# TSSOP16_a_DIP.net
KiCad netlist of a schematic drawn in EAGLE
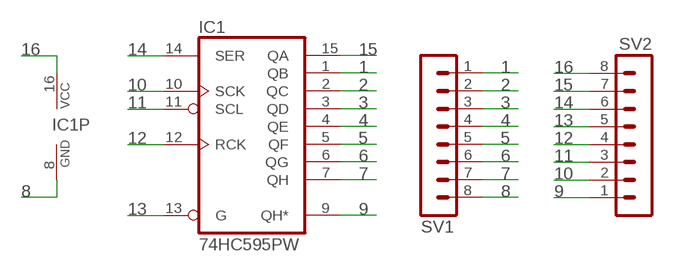
[diagram p0: schematic, sheet 1]

(export (version "E")
  (design (tool "Eeschema 10.0.6"))
  (components
    (comp (ref "IC1")
      (value "74HC595PW")
      (footprint "eagle-import:TSSOP16")
      (libsource (lib "eagle-import") (part "74595PWHC"))
    )
    (comp (ref "SV1")
      (value "MA08-1")
      (footprint "eagle-import:MA08-1")
      (libsource (lib "eagle-import") (part "MA08-1"))
    )
    (comp (ref "SV2")
      (value "MA08-1")
      (footprint "eagle-import:MA08-1")
      (libsource (lib "eagle-import") (part "MA08-1"))
    )
  )
  (nets
    (net (code "1") (name "/1") (class "Default")
      (node (ref "IC1") (pin "1") (pinfunction "QB_1") (pintype "tri_state"))
      (node (ref "SV1") (pin "1") (pinfunction "1_1") (pintype "passive"))
    )
    (net (code "2") (name "/2") (class "Default")
      (node (ref "IC1") (pin "2") (pinfunction "QC_2") (pintype "tri_state"))
      (node (ref "SV1") (pin "2") (pinfunction "2_2") (pintype "passive"))
    )
    (net (code "3") (name "/3") (class "Default")
      (node (ref "IC1") (pin "3") (pinfunction "QD_3") (pintype "tri_state"))
      (node (ref "SV1") (pin "3") (pinfunction "3_3") (pintype "passive"))
    )
    (net (code "4") (name "/4") (class "Default")
      (node (ref "IC1") (pin "4") (pinfunction "QE_4") (pintype "tri_state"))
      (node (ref "SV1") (pin "4") (pinfunction "4_4") (pintype "passive"))
    )
    (net (code "5") (name "/5") (class "Default")
      (node (ref "IC1") (pin "5") (pinfunction "QF_5") (pintype "tri_state"))
      (node (ref "SV1") (pin "5") (pinfunction "5_5") (pintype "passive"))
    )
    (net (code "6") (name "/6") (class "Default")
      (node (ref "IC1") (pin "6") (pinfunction "QG_6") (pintype "tri_state"))
      (node (ref "SV1") (pin "6") (pinfunction "6_6") (pintype "passive"))
    )
    (net (code "7") (name "/7") (class "Default")
      (node (ref "IC1") (pin "7") (pinfunction "QH_7") (pintype "tri_state"))
      (node (ref "SV1") (pin "7") (pinfunction "7_7") (pintype "passive"))
    )
    (net (code "8") (name "/8") (class "Default")
      (node (ref "IC1") (pin "8") (pinfunction "GND_8") (pintype "power_in"))
      (node (ref "SV1") (pin "8") (pinfunction "8_8") (pintype "passive"))
    )
    (net (code "9") (name "/9") (class "Default")
      (node (ref "IC1") (pin "9") (pinfunction "QH*_9") (pintype "tri_state"))
      (node (ref "SV2") (pin "1") (pinfunction "1_1") (pintype "passive"))
    )
    (net (code "10") (name "/10") (class "Default")
      (node (ref "IC1") (pin "10") (pinfunction "SCK_10") (pintype "input"))
      (node (ref "SV2") (pin "2") (pinfunction "2_2") (pintype "passive"))
    )
    (net (code "11") (name "/11") (class "Default")
      (node (ref "IC1") (pin "11") (pinfunction "SCL_11") (pintype "input"))
      (node (ref "SV2") (pin "3") (pinfunction "3_3") (pintype "passive"))
    )
    (net (code "12") (name "/12") (class "Default")
      (node (ref "IC1") (pin "12") (pinfunction "RCK_12") (pintype "input"))
      (node (ref "SV2") (pin "4") (pinfunction "4_4") (pintype "passive"))
    )
    (net (code "13") (name "/13") (class "Default")
      (node (ref "IC1") (pin "13") (pinfunction "G_13") (pintype "input"))
      (node (ref "SV2") (pin "5") (pinfunction "5_5") (pintype "passive"))
    )
    (net (code "14") (name "/14") (class "Default")
      (node (ref "IC1") (pin "14") (pinfunction "SER_14") (pintype "input"))
      (node (ref "SV2") (pin "6") (pinfunction "6_6") (pintype "passive"))
    )
    (net (code "15") (name "/15") (class "Default")
      (node (ref "IC1") (pin "15") (pinfunction "QA_15") (pintype "tri_state"))
      (node (ref "SV2") (pin "7") (pinfunction "7_7") (pintype "passive"))
    )
    (net (code "16") (name "/16") (class "Default")
      (node (ref "IC1") (pin "16") (pinfunction "VCC_16") (pintype "power_in"))
      (node (ref "SV2") (pin "8") (pinfunction "8_8") (pintype "passive"))
    )
  )
)
